# PWRCTRL_RELAY_PWM_28V2A.net
KiCad netlist of a schematic drawn in Altium Designer
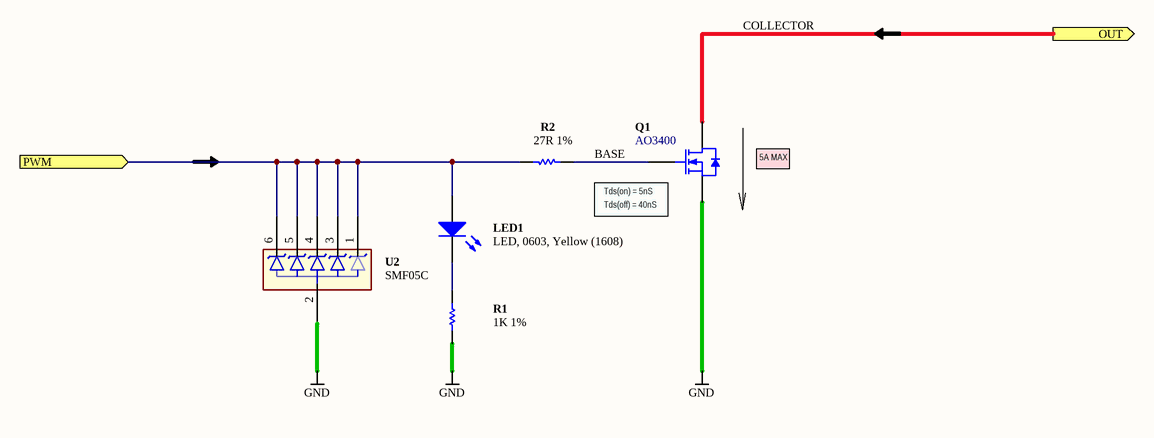
[diagram p0: PWRCTRL_RELAY_PWM_28V2A.SchDoc]

(export (version "E")
  (design (tool "Eeschema 10.0.6"))
  (components
    (comp (ref "LED1")
      (value "LED, 0603, Yellow (1608)")
      (footprint "0603LED_YELLOW")
      (libsource (lib "AltiumDesignLibrary") (part "DIO-LED-1S"))
    )
    (comp (ref "Q1")
      (value "AO3400")
      (footprint "SOT95P230-3D")
      (description "N-channel Enhancement Mode Field-effect Transistor;  5.8A/30V")
      (libsource (lib "AltiumDesignLibrary") (part "N-Channel-FET"))
    )
    (comp (ref "R1")
      (value "1K 1%")
      (footprint "RESC1005-STAR")
      (description "Resistor, 1K 1% 0402 (1005)")
      (fields (field (name "TOLERANCE") "1 %"))
      (libsource (lib "AltiumDesignLibrary") (part "RES"))
    )
    (comp (ref "R2")
      (value "27R 1%")
      (footprint "RESC1005-STAR")
      (description "Resistor, 27R 1% 0402 (1005)")
      (fields (field (name "TOLERANCE") "1%"))
      (libsource (lib "AltiumDesignLibrary") (part "RES"))
    )
    (comp (ref "U2")
      (value "SMF05C")
      (footprint "SC70_6L")
      (description "TVS Diode Array  For ESD and Latch-Up Protection")
      (libsource (lib "AltiumDesignLibrary") (part "SMF05C"))
    )
  )
  (nets
    (net (code "1") (name "/BASE") (class "Default")
      (node (ref "Q1") (pin "1") (pinfunction "G_1") (pintype "passive"))
      (node (ref "R2") (pin "2") (pinfunction "2_2") (pintype "passive"))
    )
    (net (code "2") (name "/COLLECTOR") (class "Default")
      (node (ref "Q1") (pin "2") (pinfunction "D_2") (pintype "passive"))
    )
    (net (code "3") (name "/PWM") (class "Default")
      (node (ref "LED1") (pin "1") (pinfunction "A_1") (pintype "passive"))
      (node (ref "R2") (pin "1") (pinfunction "1_1") (pintype "passive"))
      (node (ref "U2") (pin "1") (pinfunction "1_1") (pintype "passive"))
      (node (ref "U2") (pin "3") (pinfunction "3_3") (pintype "passive"))
      (node (ref "U2") (pin "4") (pinfunction "4_4") (pintype "passive"))
      (node (ref "U2") (pin "5") (pinfunction "5_5") (pintype "passive"))
      (node (ref "U2") (pin "6") (pinfunction "6_6") (pintype "passive"))
    )
    (net (code "4") (name "GND") (class "Default")
      (node (ref "Q1") (pin "3") (pinfunction "S_3") (pintype "passive"))
      (node (ref "R1") (pin "1") (pinfunction "1_1") (pintype "passive"))
      (node (ref "U2") (pin "2") (pinfunction "2_2") (pintype "passive"))
    )
    (net (code "5") (name "Net-(LED1-K)") (class "Default")
      (node (ref "LED1") (pin "2") (pinfunction "K_2") (pintype "passive"))
      (node (ref "R1") (pin "2") (pinfunction "2_2") (pintype "passive"))
    )
  )
)
